# sensor_v0_2.net
KiCad netlist of a schematic drawn in EAGLE
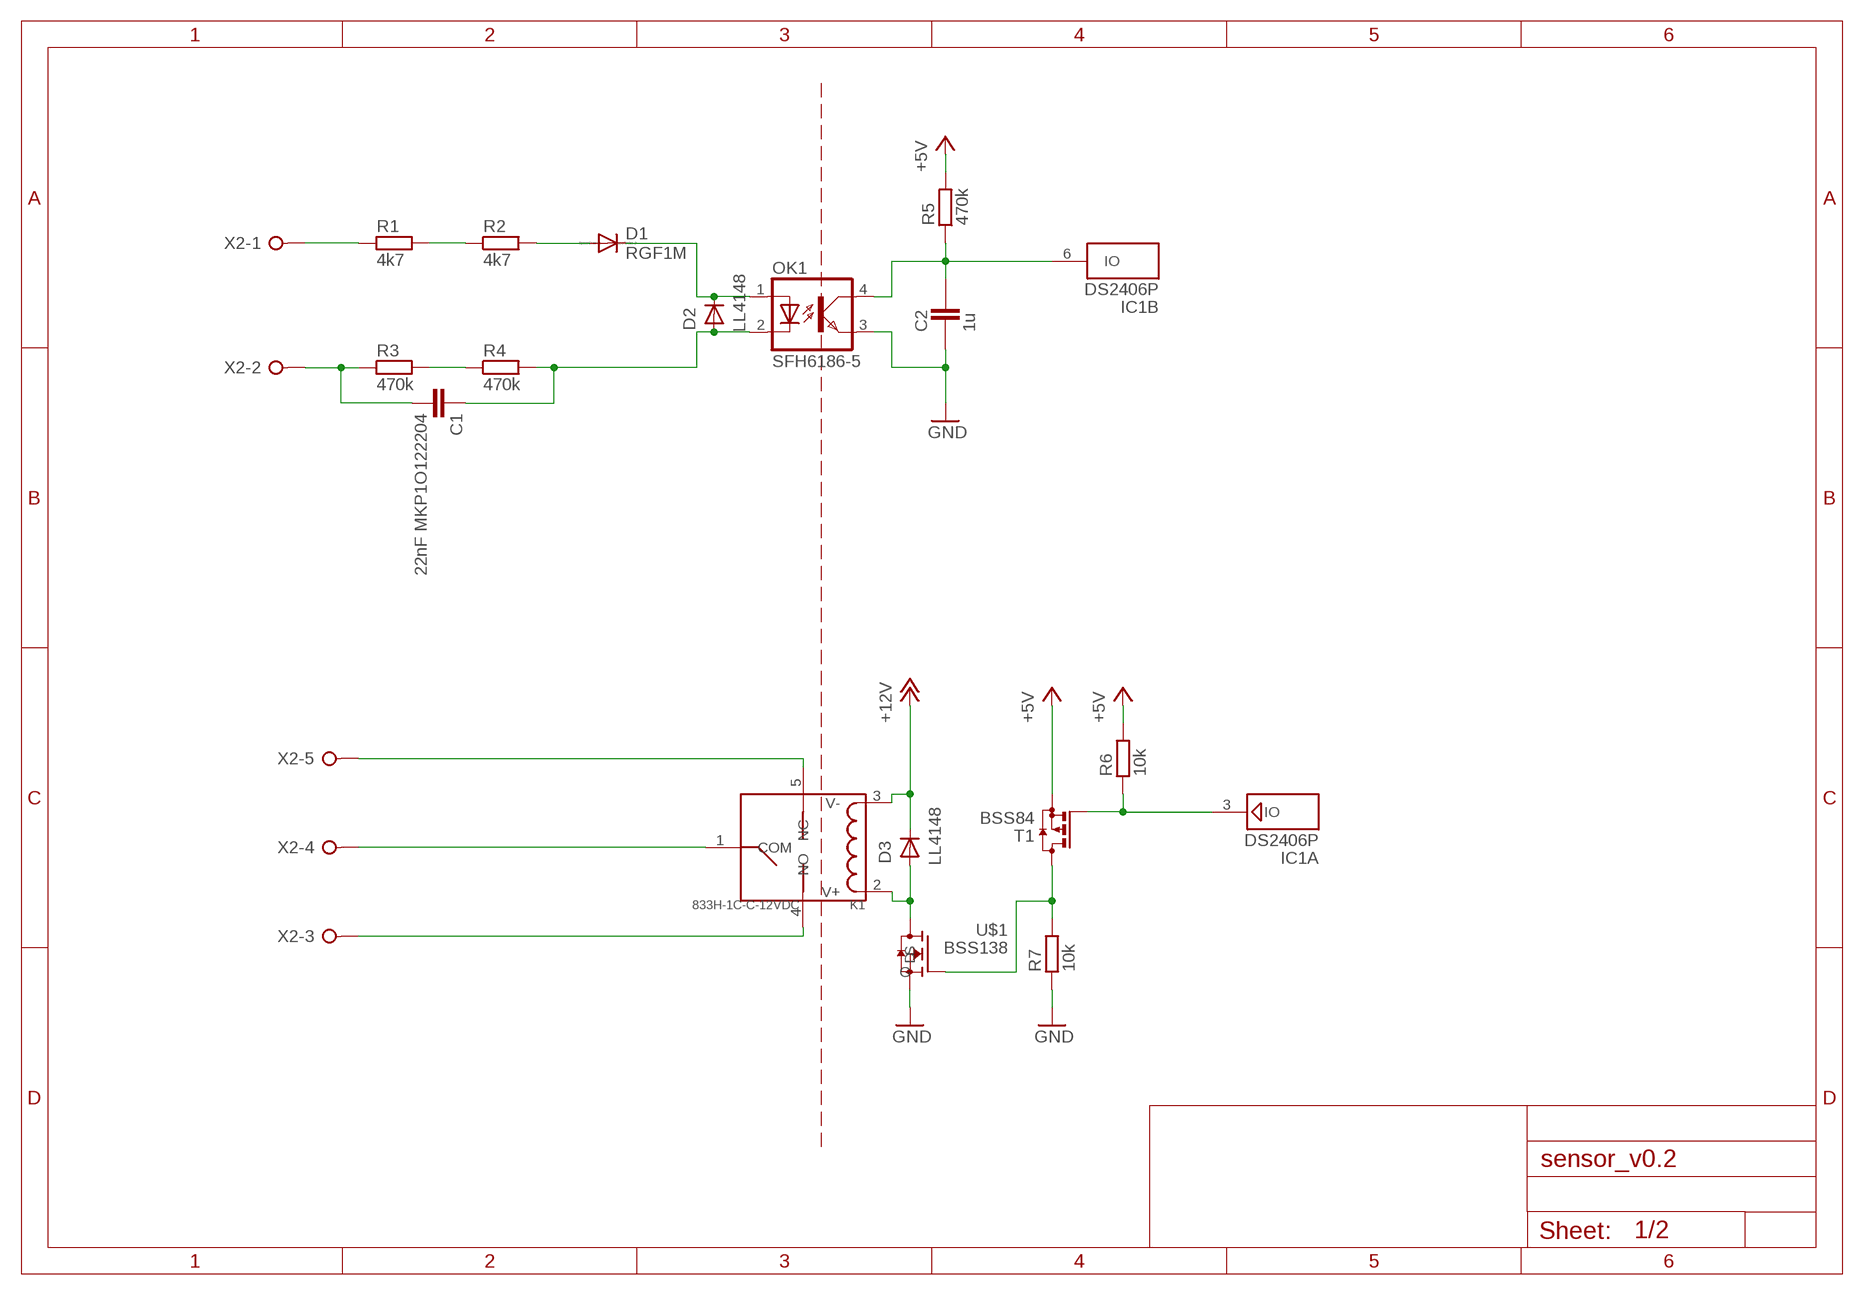
[diagram p0: schematic, sheet 1]
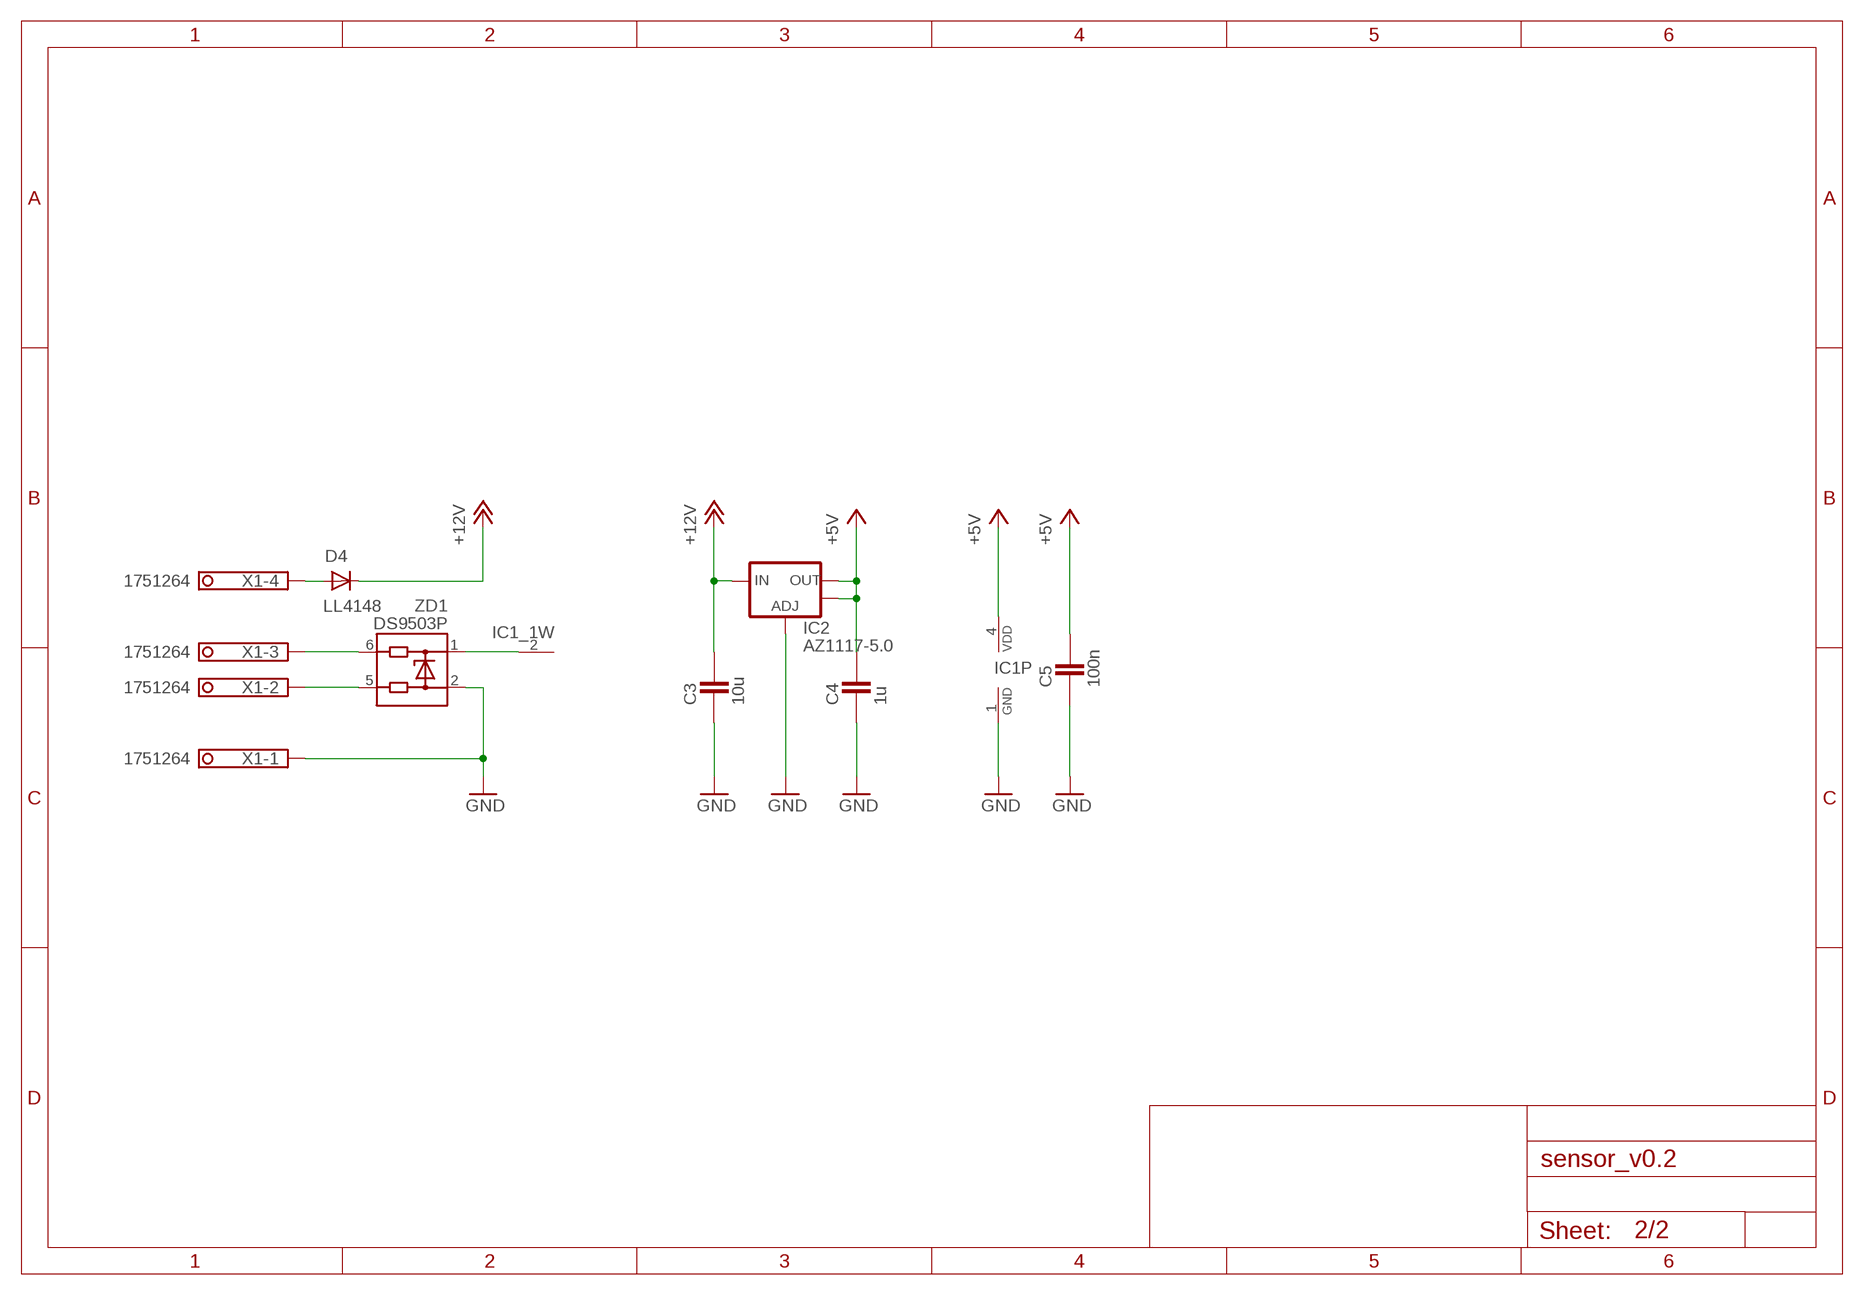
[diagram p1: schematic, sheet 2]

(export (version "E")
  (design (tool "Eeschema 10.0.6"))
  (components
    (comp (ref "C1")
      (value "22nF MKP1O122204")
      (footprint "eagle-import:C150-064X183")
      (libsource (lib "eagle-import") (part "C-EU150-064X183"))
    )
    (comp (ref "C2")
      (value "1u")
      (footprint "eagle-import:CAPC1608X92N")
      (libsource (lib "eagle-import") (part "CAPACITOR_0603"))
    )
    (comp (ref "D1")
      (value "RGF1M")
      (footprint "eagle-import:DO214BA")
      (libsource (lib "eagle-import") (part "DIODE-DO214BA"))
    )
    (comp (ref "D2")
      (value "LL4148")
      (footprint "eagle-import:SOD80C")
      (libsource (lib "eagle-import") (part "PMLL4148L"))
    )
    (comp (ref "D3")
      (value "LL4148")
      (footprint "eagle-import:SOD80C")
      (libsource (lib "eagle-import") (part "PMLL4148L"))
    )
    (comp (ref "IC1")
      (value "DS2406P")
      (footprint "eagle-import:TSOC6")
      (libsource (lib "eagle-import") (part "DS2406P"))
    )
    (comp (ref "K1")
      (value "833H-1C-C-12VDC")
      (footprint "eagle-import:REY5-19.0X15.0X15.0MM")
      (fields (field (name "MPN") "HLS8L-DC3V-S-C"))
      (libsource (lib "eagle-import") (part "RELAY-HLS8L-DC3V-S-C(5P-19X15MM)"))
    )
    (comp (ref "OK1")
      (value "SFH6186-5")
      (footprint "eagle-import:SMD4")
      (libsource (lib "eagle-import") (part "SFH618?6-5"))
    )
    (comp (ref "R1")
      (value "4k7")
      (footprint "eagle-import:RESC6432X70N")
      (libsource (lib "eagle-import") (part "RESISTOR_2512"))
    )
    (comp (ref "R2")
      (value "4k7")
      (footprint "eagle-import:RESC6432X70N")
      (libsource (lib "eagle-import") (part "RESISTOR_2512"))
    )
    (comp (ref "R3")
      (value "470k")
      (footprint "eagle-import:RESC6432X70N")
      (libsource (lib "eagle-import") (part "RESISTOR_2512"))
    )
    (comp (ref "R4")
      (value "470k")
      (footprint "eagle-import:RESC6432X70N")
      (libsource (lib "eagle-import") (part "RESISTOR_2512"))
    )
    (comp (ref "R5")
      (value "470k")
      (footprint "eagle-import:RESC1005X40AN")
      (libsource (lib "eagle-import") (part "RESISTOR_0402"))
    )
    (comp (ref "R6")
      (value "10k")
      (footprint "eagle-import:RESC1005X40AN")
      (libsource (lib "eagle-import") (part "RESISTOR_0402"))
    )
    (comp (ref "R7")
      (value "10k")
      (footprint "eagle-import:RESC1005X40AN")
      (libsource (lib "eagle-import") (part "RESISTOR_0402"))
    )
    (comp (ref "T1")
      (value "BSS84")
      (footprint "eagle-import:SOT23")
      (libsource (lib "eagle-import") (part "BSS84"))
    )
    (comp (ref "U$1")
      (value "BSS138")
      (footprint "eagle-import:BSS138")
      (libsource (lib "eagle-import") (part "BSS138"))
    )
    (comp (ref "X2")
      (value "W237-05P")
      (footprint "eagle-import:W237-5P")
      (libsource (lib "eagle-import") (part "W237-05P"))
    )
    (comp (ref "C3")
      (value "10u")
      (footprint "eagle-import:CAPC2012X145AN")
      (libsource (lib "eagle-import") (part "CAPACITOR_0805"))
    )
    (comp (ref "C4")
      (value "1u")
      (footprint "eagle-import:CAPC1608X92N")
      (libsource (lib "eagle-import") (part "CAPACITOR_0603"))
    )
    (comp (ref "C5")
      (value "100n")
      (footprint "eagle-import:CAPC1005X60N")
      (libsource (lib "eagle-import") (part "CAPACITOR_0402"))
    )
    (comp (ref "D4")
      (value "LL4148")
      (footprint "eagle-import:SOD80C")
      (libsource (lib "eagle-import") (part "PMLL4148L"))
    )
    (comp (ref "IC2")
      (value "AZ1117-5.0")
      (footprint "eagle-import:SOT223")
      (libsource (lib "eagle-import") (part "V_REG_LM1117SOT223"))
    )
    (comp (ref "X1")
      (value "1751264")
      (footprint "eagle-import:1751264")
      (libsource (lib "eagle-import") (part "1751264"))
    )
    (comp (ref "ZD1")
      (value "DS9503P")
      (footprint "eagle-import:TSOC6")
      (libsource (lib "eagle-import") (part "DS9503P"))
    )
  )
  (nets
    (net (code "1") (name "+5V") (class "Default")
      (node (ref "C4") (pin "2") (pinfunction "2_2") (pintype "passive"))
      (node (ref "C5") (pin "2") (pinfunction "2_2") (pintype "passive"))
      (node (ref "IC1") (pin "4") (pinfunction "VDD_4") (pintype "power_in"))
      (node (ref "IC2") (pin "2") (pinfunction "OUT_2") (pintype "output"))
      (node (ref "IC2") (pin "4") (pinfunction "OUT_4") (pintype "output"))
      (node (ref "R5") (pin "2") (pinfunction "2_2") (pintype "passive"))
      (node (ref "R6") (pin "2") (pinfunction "2_2") (pintype "passive"))
      (node (ref "T1") (pin "2") (pinfunction "S_2") (pintype "passive"))
    )
    (net (code "2") (name "+12V") (class "Default")
      (node (ref "C3") (pin "2") (pinfunction "2_2") (pintype "passive"))
      (node (ref "D3") (pin "1") (pinfunction "K_1") (pintype "passive"))
      (node (ref "D4") (pin "1") (pinfunction "K_1") (pintype "passive"))
      (node (ref "IC2") (pin "3") (pinfunction "IN_3") (pintype "input"))
      (node (ref "K1") (pin "3") (pinfunction "V-_3") (pintype "bidirectional"))
    )
    (net (code "3") (name "GND") (class "Default")
      (node (ref "C2") (pin "1") (pinfunction "1_1") (pintype "passive"))
      (node (ref "C3") (pin "1") (pinfunction "1_1") (pintype "passive"))
      (node (ref "C4") (pin "1") (pinfunction "1_1") (pintype "passive"))
      (node (ref "C5") (pin "1") (pinfunction "1_1") (pintype "passive"))
      (node (ref "IC1") (pin "1") (pinfunction "GND_1") (pintype "power_in"))
      (node (ref "IC2") (pin "1") (pinfunction "ADJ_1") (pintype "input"))
      (node (ref "OK1") (pin "3") (pinfunction "EMIT_3") (pintype "passive"))
      (node (ref "R7") (pin "1") (pinfunction "1_1") (pintype "passive"))
      (node (ref "U$1") (pin "S") (pinfunction "S_S") (pintype "passive"))
      (node (ref "X1") (pin "1") (pinfunction "K_1") (pintype "passive"))
      (node (ref "ZD1") (pin "2") (pinfunction "P$2_2") (pintype "passive"))
    )
    (net (code "4") (name "Net-(D1-PadA)") (class "Default")
      (node (ref "D1") (pin "A") (pinfunction "A_A") (pintype "passive"))
      (node (ref "R2") (pin "2") (pinfunction "2_2") (pintype "passive"))
    )
    (net (code "5") (name "Net-(D2-A)") (class "Default")
      (node (ref "C1") (pin "1") (pinfunction "1_1") (pintype "passive"))
      (node (ref "D2") (pin "2") (pinfunction "A_2") (pintype "passive"))
      (node (ref "OK1") (pin "2") (pinfunction "C_2") (pintype "passive"))
      (node (ref "R4") (pin "2") (pinfunction "2_2") (pintype "passive"))
    )
    (net (code "6") (name "Net-(D2-K)") (class "Default")
      (node (ref "D1") (pin "C") (pinfunction "C_C") (pintype "passive"))
      (node (ref "D2") (pin "1") (pinfunction "K_1") (pintype "passive"))
      (node (ref "OK1") (pin "1") (pinfunction "A_1") (pintype "passive"))
    )
    (net (code "7") (name "Net-(D3-A)") (class "Default")
      (node (ref "D3") (pin "2") (pinfunction "A_2") (pintype "passive"))
      (node (ref "K1") (pin "2") (pinfunction "V+_2") (pintype "bidirectional"))
      (node (ref "U$1") (pin "D") (pinfunction "D_D") (pintype "passive"))
    )
    (net (code "8") (name "Net-(D4-A)") (class "Default")
      (node (ref "D4") (pin "2") (pinfunction "A_2") (pintype "passive"))
      (node (ref "X1") (pin "4") (pinfunction "K_4") (pintype "passive"))
    )
    (net (code "9") (name "Net-(IC1A-IO)") (class "Default")
      (node (ref "IC1") (pin "3") (pinfunction "IO_3") (pintype "open_collector"))
      (node (ref "R6") (pin "1") (pinfunction "1_1") (pintype "passive"))
      (node (ref "T1") (pin "1") (pinfunction "G_1") (pintype "passive"))
    )
    (net (code "10") (name "Net-(IC1B-IO)") (class "Default")
      (node (ref "C2") (pin "2") (pinfunction "2_2") (pintype "passive"))
      (node (ref "IC1") (pin "6") (pinfunction "IO_6") (pintype "open_collector"))
      (node (ref "OK1") (pin "4") (pinfunction "COL_4") (pintype "passive"))
      (node (ref "R5") (pin "1") (pinfunction "1_1") (pintype "passive"))
    )
    (net (code "11") (name "Net-(IC1D-1W)") (class "Default")
      (node (ref "IC1") (pin "2") (pinfunction "1W_2") (pintype "power_in"))
      (node (ref "ZD1") (pin "1") (pinfunction "P$1_1") (pintype "passive"))
    )
    (net (code "12") (name "Net-(K1-COM)") (class "Default")
      (node (ref "K1") (pin "1") (pinfunction "COM_1") (pintype "bidirectional"))
      (node (ref "X2") (pin "4") (pinfunction "KL_4") (pintype "passive"))
    )
    (net (code "13") (name "Net-(K1-NC)") (class "Default")
      (node (ref "K1") (pin "5") (pinfunction "NC_5") (pintype "bidirectional"))
      (node (ref "X2") (pin "5") (pinfunction "KL_5") (pintype "passive"))
    )
    (net (code "14") (name "Net-(K1-NO)") (class "Default")
      (node (ref "K1") (pin "4") (pinfunction "NO_4") (pintype "bidirectional"))
      (node (ref "X2") (pin "3") (pinfunction "KL_3") (pintype "passive"))
    )
    (net (code "15") (name "Net-(R1-Pad2)") (class "Default")
      (node (ref "R1") (pin "2") (pinfunction "2_2") (pintype "passive"))
      (node (ref "R2") (pin "1") (pinfunction "1_1") (pintype "passive"))
    )
    (net (code "16") (name "Net-(R3-Pad2)") (class "Default")
      (node (ref "R3") (pin "2") (pinfunction "2_2") (pintype "passive"))
      (node (ref "R4") (pin "1") (pinfunction "1_1") (pintype "passive"))
    )
    (net (code "17") (name "Net-(T1-D)") (class "Default")
      (node (ref "R7") (pin "2") (pinfunction "2_2") (pintype "passive"))
      (node (ref "T1") (pin "3") (pinfunction "D_3") (pintype "passive"))
      (node (ref "U$1") (pin "G") (pinfunction "G_G") (pintype "passive"))
    )
    (net (code "18") (name "Net-(X1B-K)") (class "Default")
      (node (ref "X1") (pin "2") (pinfunction "K_2") (pintype "passive"))
      (node (ref "ZD1") (pin "5") (pinfunction "P$3_5") (pintype "passive"))
    )
    (net (code "19") (name "Net-(X1C-K)") (class "Default")
      (node (ref "X1") (pin "3") (pinfunction "K_3") (pintype "passive"))
      (node (ref "ZD1") (pin "6") (pinfunction "P$4_6") (pintype "passive"))
    )
    (net (code "20") (name "Net-(X2A-KL)") (class "Default")
      (node (ref "R1") (pin "1") (pinfunction "1_1") (pintype "passive"))
      (node (ref "X2") (pin "1") (pinfunction "KL_1") (pintype "passive"))
    )
    (net (code "21") (name "Net-(X2B-KL)") (class "Default")
      (node (ref "C1") (pin "2") (pinfunction "2_2") (pintype "passive"))
      (node (ref "R3") (pin "1") (pinfunction "1_1") (pintype "passive"))
      (node (ref "X2") (pin "2") (pinfunction "KL_2") (pintype "passive"))
    )
  )
)
